# analogBoardV1_5.net
KiCad netlist of a schematic drawn in EAGLE
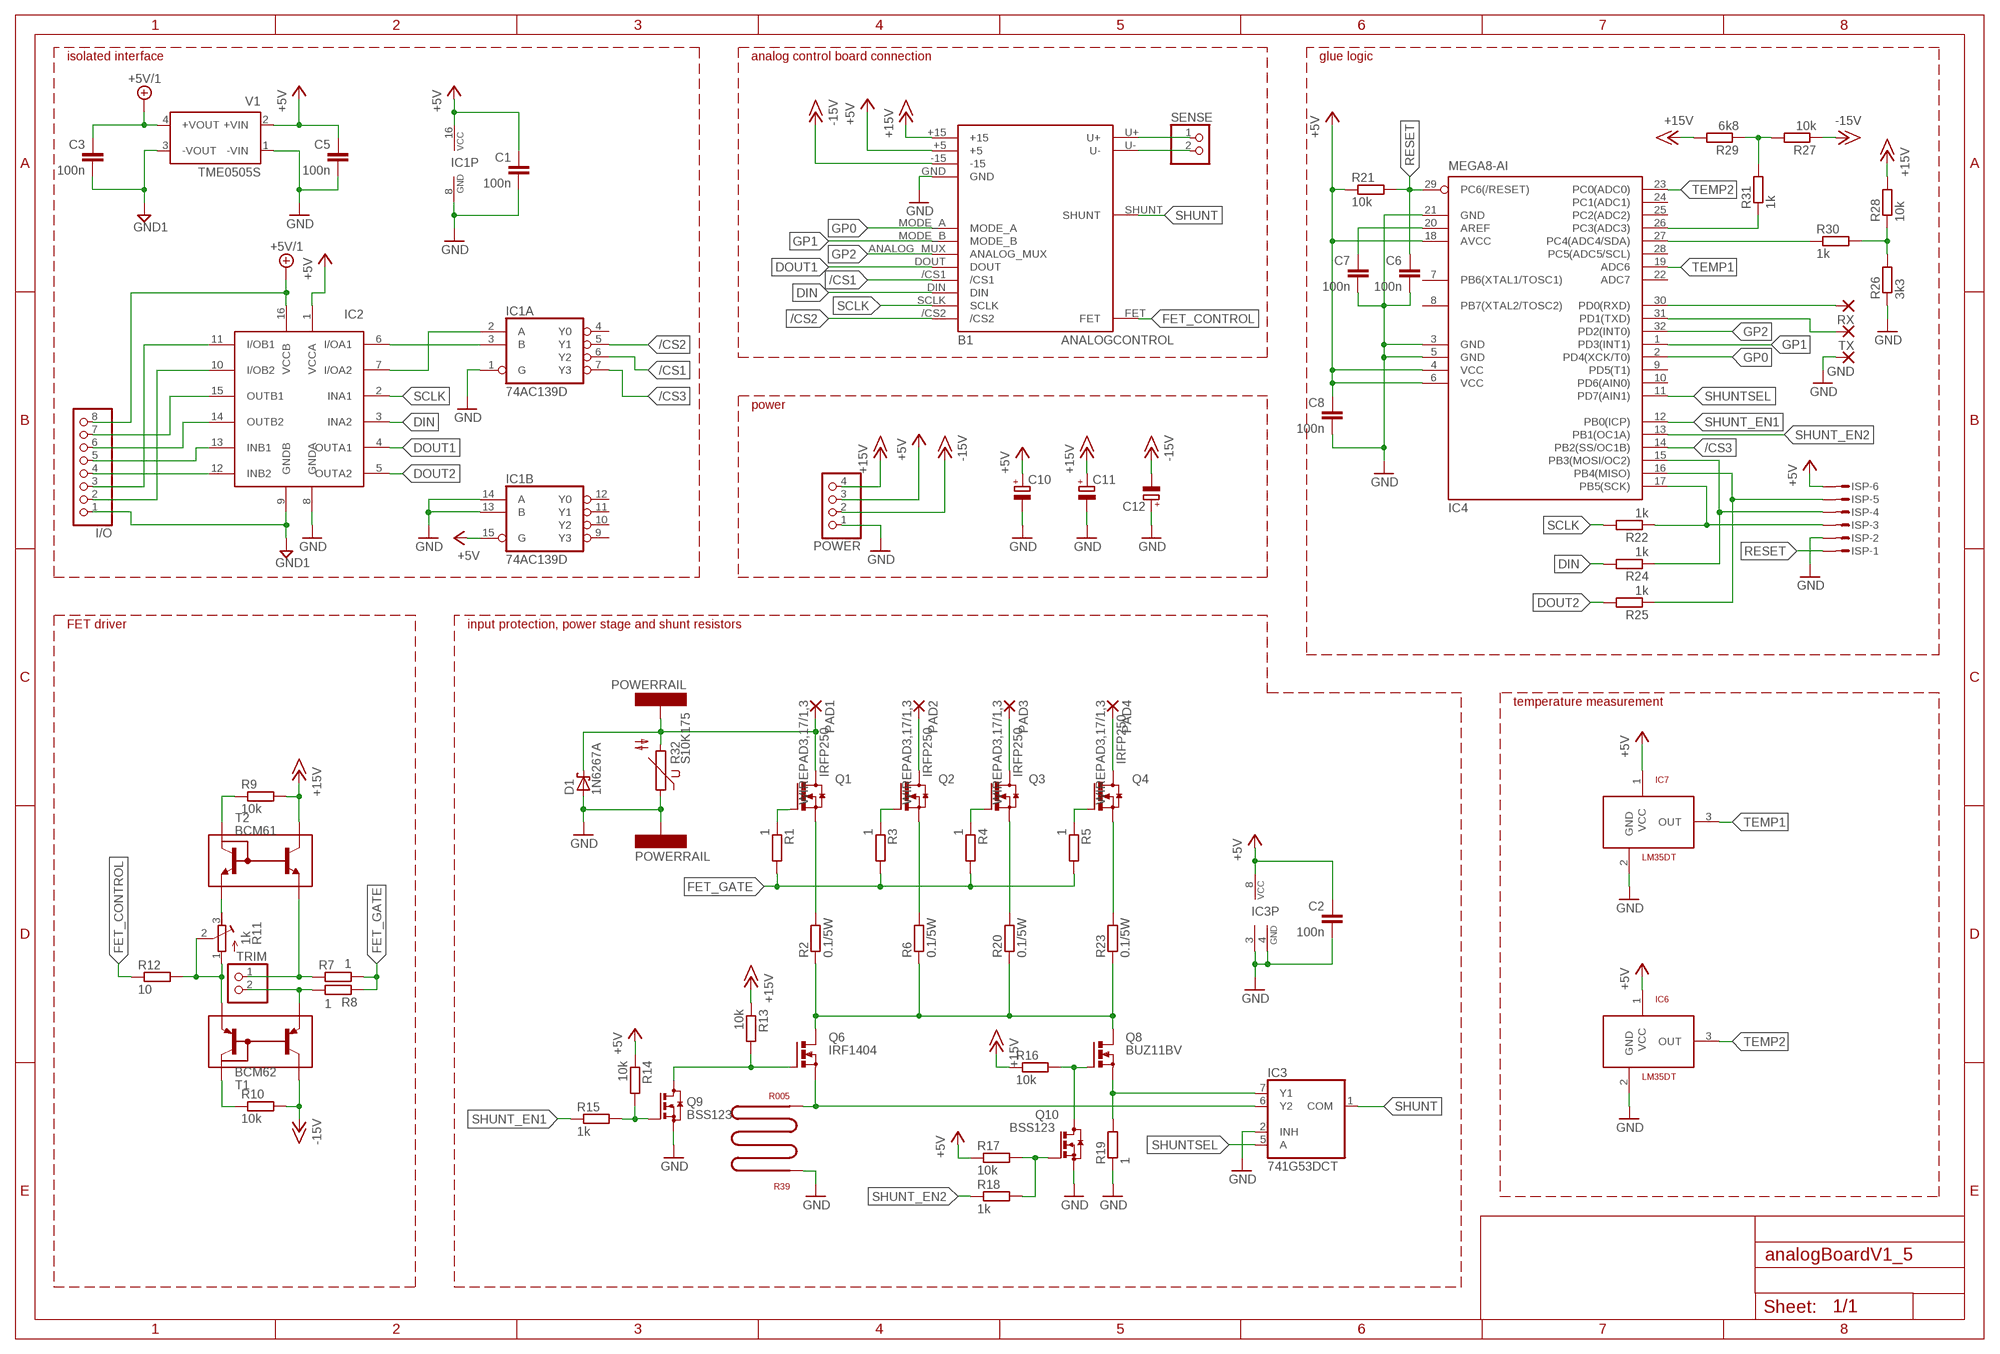
[diagram p0: schematic, sheet 1]

(export (version "E")
  (design (tool "Eeschema 10.0.6"))
  (components
    (comp (ref "B1")
      (value "ANALOGCONTROL")
      (footprint "eagle-import:ANALOGCONTROL")
      (libsource (lib "eagle-import") (part "ANALOGCONTROL"))
    )
    (comp (ref "C1")
      (value "100n")
      (footprint "eagle-import:C0603K")
      (libsource (lib "eagle-import") (part "C-EUC0603K"))
    )
    (comp (ref "C2")
      (value "100n")
      (footprint "eagle-import:C0603K")
      (libsource (lib "eagle-import") (part "C-EUC0603K"))
    )
    (comp (ref "C3")
      (value "100n")
      (footprint "eagle-import:C0603K")
      (libsource (lib "eagle-import") (part "C-EUC0603K"))
    )
    (comp (ref "C5")
      (value "100n")
      (footprint "eagle-import:C0603K")
      (libsource (lib "eagle-import") (part "C-EUC0603K"))
    )
    (comp (ref "C6")
      (value "100n")
      (footprint "eagle-import:C0603K")
      (libsource (lib "eagle-import") (part "C-EUC0603K"))
    )
    (comp (ref "C7")
      (value "100n")
      (footprint "eagle-import:C0603K")
      (libsource (lib "eagle-import") (part "C-EUC0603K"))
    )
    (comp (ref "C8")
      (value "100n")
      (footprint "eagle-import:C0603K")
      (libsource (lib "eagle-import") (part "C-EUC0603K"))
    )
    (comp (ref "C10")
      (value "CPOL-EUE2.5-6")
      (footprint "eagle-import:E2,5-6")
      (libsource (lib "eagle-import") (part "CPOL-EUE2.5-6"))
    )
    (comp (ref "C11")
      (value "CPOL-EUE2.5-6")
      (footprint "eagle-import:E2,5-6")
      (libsource (lib "eagle-import") (part "CPOL-EUE2.5-6"))
    )
    (comp (ref "C12")
      (value "CPOL-EUE2.5-6")
      (footprint "eagle-import:E2,5-6")
      (libsource (lib "eagle-import") (part "CPOL-EUE2.5-6"))
    )
    (comp (ref "D1")
      (value "1N6267A")
      (footprint "eagle-import:C4111-15")
      (libsource (lib "eagle-import") (part "1N6267A"))
    )
    (comp (ref "GND")
      (value "SMD2")
      (footprint "eagle-import:SMD1,27-2,54")
      (libsource (lib "eagle-import") (part "SMD2"))
    )
    (comp (ref "I/O")
      (value "PINHD-1X8")
      (footprint "eagle-import:1X08")
      (libsource (lib "eagle-import") (part "PINHD-1X8"))
    )
    (comp (ref "IC1")
      (value "74AC139D")
      (footprint "eagle-import:SO16")
      (libsource (lib "eagle-import") (part "74139DAC"))
    )
    (comp (ref "IC2")
      (value "MAX14850")
      (footprint "eagle-import:SOIC16N")
      (libsource (lib "eagle-import") (part "MAX14850"))
    )
    (comp (ref "IC3")
      (value "741G53DCT")
      (footprint "eagle-import:DCT_R-PDSO-G8")
      (libsource (lib "eagle-import") (part "741G53DCT"))
    )
    (comp (ref "IC4")
      (value "MEGA8-AI")
      (footprint "eagle-import:TQFP32-08")
      (fields (field (name "MPN") "ATMEGA8-16AU"))
      (libsource (lib "eagle-import") (part "MEGA8-AI"))
    )
    (comp (ref "IC6")
      (value "LM35DT")
      (footprint "eagle-import:TO220V")
      (libsource (lib "eagle-import") (part "LM35DT"))
    )
    (comp (ref "IC7")
      (value "LM35DT")
      (footprint "eagle-import:TO220V")
      (libsource (lib "eagle-import") (part "LM35DT"))
    )
    (comp (ref "ISP")
      (value "MICROMATCH-6SMF")
      (footprint "eagle-import:MMT-F-SMD-6")
      (libsource (lib "eagle-import") (part "MICROMATCH-6SMF"))
    )
    (comp (ref "PAD1")
      (value "WIREPAD3,17/1,3")
      (footprint "eagle-import:3,17_1,3")
      (libsource (lib "eagle-import") (part "WIREPAD3,17/1,3"))
    )
    (comp (ref "PAD2")
      (value "WIREPAD3,17/1,3")
      (footprint "eagle-import:3,17_1,3")
      (libsource (lib "eagle-import") (part "WIREPAD3,17/1,3"))
    )
    (comp (ref "PAD3")
      (value "WIREPAD3,17/1,3")
      (footprint "eagle-import:3,17_1,3")
      (libsource (lib "eagle-import") (part "WIREPAD3,17/1,3"))
    )
    (comp (ref "PAD4")
      (value "WIREPAD3,17/1,3")
      (footprint "eagle-import:3,17_1,3")
      (libsource (lib "eagle-import") (part "WIREPAD3,17/1,3"))
    )
    (comp (ref "POWER")
      (value "PINHD-1X4")
      (footprint "eagle-import:1X04")
      (libsource (lib "eagle-import") (part "PINHD-1X4"))
    )
    (comp (ref "Q1")
      (value "IRFP250")
      (footprint "eagle-import:TO-247AD-V")
      (libsource (lib "eagle-import") (part "IRFP250"))
    )
    (comp (ref "Q2")
      (value "IRFP250")
      (footprint "eagle-import:TO-247AD-V")
      (libsource (lib "eagle-import") (part "IRFP250"))
    )
    (comp (ref "Q3")
      (value "IRFP250")
      (footprint "eagle-import:TO-247AD-V")
      (libsource (lib "eagle-import") (part "IRFP250"))
    )
    (comp (ref "Q4")
      (value "IRFP250")
      (footprint "eagle-import:TO-247AD-V")
      (libsource (lib "eagle-import") (part "IRFP250"))
    )
    (comp (ref "Q6")
      (value "IRF1404")
      (footprint "eagle-import:TO220BV")
      (libsource (lib "eagle-import") (part "BUZ11BV"))
    )
    (comp (ref "Q8")
      (value "BUZ11BV")
      (footprint "eagle-import:TO220BV")
      (libsource (lib "eagle-import") (part "BUZ11BV"))
    )
    (comp (ref "Q9")
      (value "BSS123")
      (footprint "eagle-import:SOT23")
      (libsource (lib "eagle-import") (part "BSS123"))
    )
    (comp (ref "Q10")
      (value "BSS123")
      (footprint "eagle-import:SOT23")
      (libsource (lib "eagle-import") (part "BSS123"))
    )
    (comp (ref "R1")
      (value "1")
      (footprint "eagle-import:R0603")
      (libsource (lib "eagle-import") (part "resistor_R-EU_R0603"))
    )
    (comp (ref "R2")
      (value "0.1/5W")
      (footprint "eagle-import:5WAXIAL_H")
      (libsource (lib "eagle-import") (part "5WAXIALH"))
    )
    (comp (ref "R3")
      (value "1")
      (footprint "eagle-import:R0603")
      (libsource (lib "eagle-import") (part "resistor_R-EU_R0603"))
    )
    (comp (ref "R4")
      (value "1")
      (footprint "eagle-import:R0603")
      (libsource (lib "eagle-import") (part "resistor_R-EU_R0603"))
    )
    (comp (ref "R5")
      (value "1")
      (footprint "eagle-import:R0603")
      (libsource (lib "eagle-import") (part "resistor_R-EU_R0603"))
    )
    (comp (ref "R6")
      (value "0.1/5W")
      (footprint "eagle-import:5WAXIAL_H")
      (libsource (lib "eagle-import") (part "5WAXIALH"))
    )
    (comp (ref "R7")
      (value "1")
      (footprint "eagle-import:R0603")
      (libsource (lib "eagle-import") (part "resistor_R-EU_R0603"))
    )
    (comp (ref "R8")
      (value "1")
      (footprint "eagle-import:R0603")
      (libsource (lib "eagle-import") (part "resistor_R-EU_R0603"))
    )
    (comp (ref "R9")
      (value "10k")
      (footprint "eagle-import:R0603")
      (libsource (lib "eagle-import") (part "resistor_R-EU_R0603"))
    )
    (comp (ref "R10")
      (value "10k")
      (footprint "eagle-import:R0603")
      (libsource (lib "eagle-import") (part "resistor_R-EU_R0603"))
    )
    (comp (ref "R11")
      (value "1k")
      (footprint "eagle-import:RTRIM64W")
      (libsource (lib "eagle-import") (part "R-TRIMM64W"))
    )
    (comp (ref "R12")
      (value "10")
      (footprint "eagle-import:R0603")
      (libsource (lib "eagle-import") (part "resistor_R-EU_R0603"))
    )
    (comp (ref "R13")
      (value "10k")
      (footprint "eagle-import:R0603")
      (libsource (lib "eagle-import") (part "resistor_R-EU_R0603"))
    )
    (comp (ref "R14")
      (value "10k")
      (footprint "eagle-import:R0603")
      (libsource (lib "eagle-import") (part "resistor_R-EU_R0603"))
    )
    (comp (ref "R15")
      (value "1k")
      (footprint "eagle-import:R0603")
      (libsource (lib "eagle-import") (part "resistor_R-EU_R0603"))
    )
    (comp (ref "R16")
      (value "10k")
      (footprint "eagle-import:R0603")
      (libsource (lib "eagle-import") (part "resistor_R-EU_R0603"))
    )
    (comp (ref "R17")
      (value "10k")
      (footprint "eagle-import:R0603")
      (libsource (lib "eagle-import") (part "resistor_R-EU_R0603"))
    )
    (comp (ref "R18")
      (value "1k")
      (footprint "eagle-import:R0603")
      (libsource (lib "eagle-import") (part "resistor_R-EU_R0603"))
    )
    (comp (ref "R19")
      (value "1")
      (footprint "eagle-import:0414_15")
      (libsource (lib "eagle-import") (part "R-EU_0414/15"))
    )
    (comp (ref "R20")
      (value "0.1/5W")
      (footprint "eagle-import:5WAXIAL_H")
      (libsource (lib "eagle-import") (part "5WAXIALH"))
    )
    (comp (ref "R21")
      (value "10k")
      (footprint "eagle-import:R0603")
      (libsource (lib "eagle-import") (part "resistor_R-EU_R0603"))
    )
    (comp (ref "R22")
      (value "1k")
      (footprint "eagle-import:R0603")
      (libsource (lib "eagle-import") (part "resistor_R-EU_R0603"))
    )
    (comp (ref "R23")
      (value "0.1/5W")
      (footprint "eagle-import:5WAXIAL_H")
      (libsource (lib "eagle-import") (part "5WAXIALH"))
    )
    (comp (ref "R24")
      (value "1k")
      (footprint "eagle-import:R0603")
      (libsource (lib "eagle-import") (part "resistor_R-EU_R0603"))
    )
    (comp (ref "R25")
      (value "1k")
      (footprint "eagle-import:R0603")
      (libsource (lib "eagle-import") (part "resistor_R-EU_R0603"))
    )
    (comp (ref "R26")
      (value "3k3")
      (footprint "eagle-import:R0603")
      (libsource (lib "eagle-import") (part "resistor_R-EU_R0603"))
    )
    (comp (ref "R27")
      (value "10k")
      (footprint "eagle-import:R0603")
      (libsource (lib "eagle-import") (part "resistor_R-EU_R0603"))
    )
    (comp (ref "R28")
      (value "10k")
      (footprint "eagle-import:R0603")
      (libsource (lib "eagle-import") (part "resistor_R-EU_R0603"))
    )
    (comp (ref "R29")
      (value "6k8")
      (footprint "eagle-import:R0603")
      (libsource (lib "eagle-import") (part "resistor_R-EU_R0603"))
    )
    (comp (ref "R30")
      (value "1k")
      (footprint "eagle-import:R0603")
      (libsource (lib "eagle-import") (part "resistor_R-EU_R0603"))
    )
    (comp (ref "R31")
      (value "1k")
      (footprint "eagle-import:R0603")
      (libsource (lib "eagle-import") (part "resistor_R-EU_R0603"))
    )
    (comp (ref "R32")
      (value "S10K175")
      (footprint "eagle-import:S10K175")
      (libsource (lib "eagle-import") (part "S10K175"))
    )
    (comp (ref "R39")
      (value "R005")
      (footprint "eagle-import:PWR4412-2S")
      (libsource (lib "eagle-import") (part "SHUNTPWR"))
    )
    (comp (ref "RX")
      (value "SMD2")
      (footprint "eagle-import:SMD1,27-2,54")
      (libsource (lib "eagle-import") (part "SMD2"))
    )
    (comp (ref "SENSE")
      (value "PINHD-1X2")
      (footprint "eagle-import:1X02")
      (libsource (lib "eagle-import") (part "PINHD-1X2"))
    )
    (comp (ref "T1")
      (value "BCM62")
      (footprint "eagle-import:SOT143B")
      (libsource (lib "eagle-import") (part "BCM62"))
    )
    (comp (ref "T2")
      (value "BCM61")
      (footprint "eagle-import:SOT143B")
      (libsource (lib "eagle-import") (part "BCM61"))
    )
    (comp (ref "TRIM")
      (value "PINHD-1X2")
      (footprint "eagle-import:1X02")
      (libsource (lib "eagle-import") (part "PINHD-1X2"))
    )
    (comp (ref "TX")
      (value "SMD2")
      (footprint "eagle-import:SMD1,27-2,54")
      (libsource (lib "eagle-import") (part "SMD2"))
    )
    (comp (ref "U$1")
      (value "POWERRAIL")
      (footprint "eagle-import:POWERRAIL")
      (libsource (lib "eagle-import") (part "POWERRAIL"))
    )
    (comp (ref "U$2")
      (value "POWERRAIL")
      (footprint "eagle-import:POWERRAIL")
      (libsource (lib "eagle-import") (part "POWERRAIL"))
    )
    (comp (ref "V1")
      (value "TME0505S")
      (footprint "eagle-import:TME")
      (fields (field (name "MPN") "TME 0505S"))
      (libsource (lib "eagle-import") (part "TME?0505S"))
    )
  )
  (nets
    (net (code "1") (name "+5V") (class "Default")
      (node (ref "B1") (pin "+5") (pinfunction "+5_+5") (pintype "bidirectional"))
      (node (ref "C1") (pin "1") (pinfunction "1_1") (pintype "passive"))
      (node (ref "C10") (pin "+") (pinfunction "+_+") (pintype "passive"))
      (node (ref "C2") (pin "1") (pinfunction "1_1") (pintype "passive"))
      (node (ref "C5") (pin "1") (pinfunction "1_1") (pintype "passive"))
      (node (ref "C8") (pin "1") (pinfunction "1_1") (pintype "passive"))
      (node (ref "IC1") (pin "15") (pinfunction "G_15") (pintype "input"))
      (node (ref "IC1") (pin "16") (pinfunction "VCC_16") (pintype "power_in"))
      (node (ref "IC2") (pin "1") (pinfunction "VCCA_1") (pintype "bidirectional"))
      (node (ref "IC3") (pin "8") (pinfunction "VCC_8") (pintype "power_in"))
      (node (ref "IC4") (pin "18") (pinfunction "AVCC_18") (pintype "power_in"))
      (node (ref "IC4") (pin "4") (pinfunction "VCC_4") (pintype "power_in"))
      (node (ref "IC4") (pin "6") (pinfunction "VCC_6") (pintype "power_in"))
      (node (ref "IC6") (pin "1") (pinfunction "VCC_1") (pintype "bidirectional"))
      (node (ref "IC7") (pin "1") (pinfunction "VCC_1") (pintype "bidirectional"))
      (node (ref "ISP") (pin "6") (pinfunction "S_6") (pintype "passive"))
      (node (ref "POWER") (pin "3") (pinfunction "3_3") (pintype "passive"))
      (node (ref "R14") (pin "1") (pinfunction "1_1") (pintype "passive"))
      (node (ref "R17") (pin "1") (pinfunction "1_1") (pintype "passive"))
      (node (ref "R21") (pin "1") (pinfunction "1_1") (pintype "passive"))
      (node (ref "V1") (pin "2") (pinfunction "+VIN_2") (pintype "passive"))
    )
    (net (code "2") (name "+5V{slash}1") (class "Default")
      (node (ref "C3") (pin "1") (pinfunction "1_1") (pintype "passive"))
      (node (ref "I/O") (pin "8") (pinfunction "8_8") (pintype "passive"))
      (node (ref "IC2") (pin "16") (pinfunction "VCCB_16") (pintype "bidirectional"))
      (node (ref "V1") (pin "4") (pinfunction "+VOUT_4") (pintype "passive"))
    )
    (net (code "3") (name "+15V") (class "Default")
      (node (ref "B1") (pin "+15") (pinfunction "+15_+15") (pintype "bidirectional"))
      (node (ref "C11") (pin "+") (pinfunction "+_+") (pintype "passive"))
      (node (ref "POWER") (pin "4") (pinfunction "4_4") (pintype "passive"))
      (node (ref "R13") (pin "1") (pinfunction "1_1") (pintype "passive"))
      (node (ref "R16") (pin "1") (pinfunction "1_1") (pintype "passive"))
      (node (ref "R28") (pin "2") (pinfunction "2_2") (pintype "passive"))
      (node (ref "R29") (pin "2") (pinfunction "2_2") (pintype "passive"))
      (node (ref "R9") (pin "2") (pinfunction "2_2") (pintype "passive"))
      (node (ref "T2") (pin "2") (pinfunction "2_2") (pintype "bidirectional"))
    )
    (net (code "4") (name "-15V") (class "Default")
      (node (ref "B1") (pin "-15") (pinfunction "-15_-15") (pintype "bidirectional"))
      (node (ref "C12") (pin "-") (pinfunction "-_-") (pintype "passive"))
      (node (ref "POWER") (pin "2") (pinfunction "2_2") (pintype "passive"))
      (node (ref "R10") (pin "2") (pinfunction "2_2") (pintype "passive"))
      (node (ref "R27") (pin "1") (pinfunction "1_1") (pintype "passive"))
      (node (ref "T1") (pin "2") (pinfunction "2_2") (pintype "bidirectional"))
    )
    (net (code "5") (name "DIN") (class "Default")
      (node (ref "B1") (pin "DIN") (pinfunction "DIN_DIN") (pintype "bidirectional"))
      (node (ref "IC2") (pin "3") (pinfunction "INA2_3") (pintype "bidirectional"))
      (node (ref "R24") (pin "2") (pinfunction "2_2") (pintype "passive"))
    )
    (net (code "6") (name "DOUT1") (class "Default")
      (node (ref "B1") (pin "DOUT") (pinfunction "DOUT_DOUT") (pintype "bidirectional"))
      (node (ref "IC2") (pin "4") (pinfunction "OUTA1_4") (pintype "bidirectional"))
    )
    (net (code "7") (name "DOUT2") (class "Default")
      (node (ref "IC2") (pin "5") (pinfunction "OUTA2_5") (pintype "bidirectional"))
      (node (ref "R25") (pin "2") (pinfunction "2_2") (pintype "passive"))
    )
    (net (code "8") (name "FET_CONTROL") (class "Default")
      (node (ref "B1") (pin "FET") (pinfunction "FET_FET") (pintype "bidirectional"))
      (node (ref "R12") (pin "1") (pinfunction "1_1") (pintype "passive"))
    )
    (net (code "9") (name "FET_GATE") (class "Default")
      (node (ref "R1") (pin "2") (pinfunction "2_2") (pintype "passive"))
      (node (ref "R3") (pin "2") (pinfunction "2_2") (pintype "passive"))
      (node (ref "R4") (pin "2") (pinfunction "2_2") (pintype "passive"))
      (node (ref "R5") (pin "2") (pinfunction "2_2") (pintype "passive"))
      (node (ref "R7") (pin "2") (pinfunction "2_2") (pintype "passive"))
      (node (ref "R8") (pin "1") (pinfunction "1_1") (pintype "passive"))
    )
    (net (code "10") (name "GND") (class "Default")
      (node (ref "B1") (pin "GND") (pinfunction "GND_GND") (pintype "bidirectional"))
      (node (ref "C1") (pin "2") (pinfunction "2_2") (pintype "passive"))
      (node (ref "C10") (pin "-") (pinfunction "-_-") (pintype "passive"))
      (node (ref "C11") (pin "-") (pinfunction "-_-") (pintype "passive"))
      (node (ref "C12") (pin "+") (pinfunction "+_+") (pintype "passive"))
      (node (ref "C2") (pin "2") (pinfunction "2_2") (pintype "passive"))
      (node (ref "C5") (pin "2") (pinfunction "2_2") (pintype "passive"))
      (node (ref "C6") (pin "2") (pinfunction "2_2") (pintype "passive"))
      (node (ref "C7") (pin "2") (pinfunction "2_2") (pintype "passive"))
      (node (ref "C8") (pin "2") (pinfunction "2_2") (pintype "passive"))
      (node (ref "D1") (pin "A") (pinfunction "A_A") (pintype "passive"))
      (node (ref "GND") (pin "1") (pinfunction "P_1") (pintype "passive"))
      (node (ref "IC1") (pin "1") (pinfunction "G_1") (pintype "input"))
      (node (ref "IC1") (pin "13") (pinfunction "B_13") (pintype "input"))
      (node (ref "IC1") (pin "14") (pinfunction "A_14") (pintype "input"))
      (node (ref "IC1") (pin "8") (pinfunction "GND_8") (pintype "power_in"))
      (node (ref "IC2") (pin "8") (pinfunction "GNDA_8") (pintype "bidirectional"))
      (node (ref "IC3") (pin "2") (pinfunction "INH_2") (pintype "input"))
      (node (ref "IC3") (pin "3") (pinfunction "GND_3") (pintype "power_in"))
      (node (ref "IC3") (pin "4") (pinfunction "GND_4") (pintype "power_in"))
      (node (ref "IC4") (pin "21") (pinfunction "GND_21") (pintype "power_in"))
      (node (ref "IC4") (pin "3") (pinfunction "GND_3") (pintype "power_in"))
      (node (ref "IC4") (pin "5") (pinfunction "GND_5") (pintype "power_in"))
      (node (ref "IC6") (pin "2") (pinfunction "GND_2") (pintype "bidirectional"))
      (node (ref "IC7") (pin "2") (pinfunction "GND_2") (pintype "bidirectional"))
      (node (ref "ISP") (pin "2") (pinfunction "S_2") (pintype "passive"))
      (node (ref "POWER") (pin "1") (pinfunction "1_1") (pintype "passive"))
      (node (ref "Q10") (pin "2") (pinfunction "S_2") (pintype "passive"))
      (node (ref "Q9") (pin "2") (pinfunction "S_2") (pintype "passive"))
      (node (ref "R19") (pin "1") (pinfunction "1_1") (pintype "passive"))
      (node (ref "R26") (pin "1") (pinfunction "1_1") (pintype "passive"))
      (node (ref "R32") (pin "1") (pinfunction "1_1") (pintype "passive"))
      (node (ref "R39") (pin "P$1") (pinfunction "P$1_P$1") (pintype "bidirectional"))
      (node (ref "U$2") (pin "1") (pinfunction "P$1_1") (pintype "bidirectional"))
      (node (ref "V1") (pin "1") (pinfunction "-VIN_1") (pintype "passive"))
    )
    (net (code "11") (name "GND1") (class "Default")
      (node (ref "C3") (pin "2") (pinfunction "2_2") (pintype "passive"))
      (node (ref "I/O") (pin "1") (pinfunction "1_1") (pintype "passive"))
      (node (ref "IC2") (pin "9") (pinfunction "GNDB_9") (pintype "bidirectional"))
      (node (ref "V1") (pin "3") (pinfunction "-VOUT_3") (pintype "passive"))
    )
    (net (code "12") (name "GP0") (class "Default")
      (node (ref "B1") (pin "MODE_A") (pinfunction "MODE_A_MODE_A") (pintype "bidirectional"))
      (node (ref "IC4") (pin "2") (pinfunction "PD4(XCK/T0)_2") (pintype "bidirectional"))
    )
    (net (code "13") (name "GP1") (class "Default")
      (node (ref "B1") (pin "MODE_B") (pinfunction "MODE_B_MODE_B") (pintype "bidirectional"))
      (node (ref "IC4") (pin "1") (pinfunction "PD3(INT1)_1") (pintype "bidirectional"))
    )
    (net (code "14") (name "GP2") (class "Default")
      (node (ref "B1") (pin "ANALOG_MUX") (pinfunction "ANALOG_MUX_ANALOG_MUX") (pintype "bidirectional"))
      (node (ref "IC4") (pin "32") (pinfunction "PD2(INT0)_32") (pintype "bidirectional"))
    )
    (net (code "15") (name "Net-(B1-PadU+)") (class "Default")
      (node (ref "B1") (pin "U+") (pinfunction "U+_U+") (pintype "bidirectional"))
      (node (ref "SENSE") (pin "1") (pinfunction "1_1") (pintype "passive"))
    )
    (net (code "16") (name "Net-(B1-PadU-)") (class "Default")
      (node (ref "B1") (pin "U-") (pinfunction "U-_U-") (pintype "bidirectional"))
      (node (ref "SENSE") (pin "2") (pinfunction "2_2") (pintype "passive"))
    )
    (net (code "17") (name "Net-(IC1A-A)") (class "Default")
      (node (ref "IC1") (pin "2") (pinfunction "A_2") (pintype "input"))
      (node (ref "IC2") (pin "7") (pinfunction "I/OA2_7") (pintype "bidirectional"))
    )
    (net (code "18") (name "Net-(IC1A-B)") (class "Default")
      (node (ref "IC1") (pin "3") (pinfunction "B_3") (pintype "input"))
      (node (ref "IC2") (pin "6") (pinfunction "I/OA1_6") (pintype "bidirectional"))
    )
    (net (code "19") (name "Net-(IC2-INB1)") (class "Default")
      (node (ref "I/O") (pin "5") (pinfunction "5_5") (pintype "passive"))
      (node (ref "IC2") (pin "13") (pinfunction "INB1_13") (pintype "bidirectional"))
    )
    (net (code "20") (name "Net-(IC2-INB2)") (class "Default")
      (node (ref "I/O") (pin "4") (pinfunction "4_4") (pintype "passive"))
      (node (ref "IC2") (pin "12") (pinfunction "INB2_12") (pintype "bidirectional"))
    )
    (net (code "21") (name "Net-(IC2-I{slash}OB1)") (class "Default")
      (node (ref "I/O") (pin "3") (pinfunction "3_3") (pintype "passive"))
      (node (ref "IC2") (pin "11") (pinfunction "I/OB1_11") (pintype "bidirectional"))
    )
    (net (code "22") (name "Net-(IC2-I{slash}OB2)") (class "Default")
      (node (ref "I/O") (pin "2") (pinfunction "2_2") (pintype "passive"))
      (node (ref "IC2") (pin "10") (pinfunction "I/OB2_10") (pintype "bidirectional"))
    )
    (net (code "23") (name "Net-(IC2-OUTB1)") (class "Default")
      (node (ref "I/O") (pin "7") (pinfunction "7_7") (pintype "passive"))
      (node (ref "IC2") (pin "15") (pinfunction "OUTB1_15") (pintype "bidirectional"))
    )
    (net (code "24") (name "Net-(IC2-OUTB2)") (class "Default")
      (node (ref "I/O") (pin "6") (pinfunction "6_6") (pintype "passive"))
      (node (ref "IC2") (pin "14") (pinfunction "OUTB2_14") (pintype "bidirectional"))
    )
    (net (code "25") (name "Net-(IC3A-Y1)") (class "Default")
      (node (ref "IC3") (pin "7") (pinfunction "Y1_7") (pintype "bidirectional"))
      (node (ref "Q8") (pin "S") (pinfunction "S_S") (pintype "passive"))
      (node (ref "R19") (pin "2") (pinfunction "2_2") (pintype "passive"))
    )
    (net (code "26") (name "Net-(IC3A-Y2)") (class "Default")
      (node (ref "IC3") (pin "6") (pinfunction "Y2_6") (pintype "bidirectional"))
      (node (ref "Q6") (pin "S") (pinfunction "S_S") (pintype "passive"))
      (node (ref "R39") (pin "P$2") (pinfunction "P$2_P$2") (pintype "bidirectional"))
    )
    (net (code "27") (name "Net-(IC4-AREF)") (class "Default")
      (node (ref "C7") (pin "1") (pinfunction "1_1") (pintype "passive"))
      (node (ref "IC4") (pin "20") (pinfunction "AREF_20") (pintype "passive"))
    )
    (net (code "28") (name "Net-(IC4-PB3(MOSI{slash}OC2))") (class "Default")
      (node (ref "IC4") (pin "15") (pinfunction "PB3(MOSI/OC2)_15") (pintype "bidirectional"))
      (node (ref "ISP") (pin "4") (pinfunction "S_4") (pintype "passive"))
      (node (ref "R24") (pin "1") (pinfunction "1_1") (pintype "passive"))
    )
    (net (code "29") (name "Net-(IC4-PB4(MISO))") (class "Default")
      (node (ref "IC4") (pin "16") (pinfunction "PB4(MISO)_16") (pintype "bidirectional"))
      (node (ref "ISP") (pin "5") (pinfunction "S_5") (pintype "passive"))
      (node (ref "R25") (pin "1") (pinfunction "1_1") (pintype "passive"))
    )
    (net (code "30") (name "Net-(IC4-PB5(SCK))") (class "Default")
      (node (ref "IC4") (pin "17") (pinfunction "PB5(SCK)_17") (pintype "bidirectional"))
      (node (ref "ISP") (pin "3") (pinfunction "S_3") (pintype "passive"))
      (node (ref "R22") (pin "1") (pinfunction "1_1") (pintype "passive"))
    )
    (net (code "31") (name "Net-(IC4-PC3(ADC3))") (class "Default")
      (node (ref "IC4") (pin "26") (pinfunction "PC3(ADC3)_26") (pintype "bidirectional"))
      (node (ref "R31") (pin "1") (pinfunction "1_1") (pintype "passive"))
    )
    (net (code "32") (name "Net-(IC4-PC4(ADC4{slash}SDA))") (class "Default")
      (node (ref "IC4") (pin "27") (pinfunction "PC4(ADC4/SDA)_27") (pintype "bidirectional"))
      (node (ref "R30") (pin "1") (pinfunction "1_1") (pintype "passive"))
    )
    (net (code "33") (name "Net-(IC4-PD0(RXD))") (class "Default")
      (node (ref "IC4") (pin "30") (pinfunction "PD0(RXD)_30") (pintype "bidirectional"))
      (node (ref "RX") (pin "1") (pinfunction "P_1") (pintype "passive"))
    )
    (net (code "34") (name "Net-(IC4-PD1(TXD))") (class "Default")
      (node (ref "IC4") (pin "31") (pinfunction "PD1(TXD)_31") (pintype "bidirectional"))
      (node (ref "TX") (pin "1") (pinfunction "P_1") (pintype "passive"))
    )
    (net (code "35") (name "Net-(PAD1-P)") (class "Default")
      (node (ref "D1") (pin "C") (pinfunction "C_C") (pintype "passive"))
      (node (ref "PAD1") (pin "1") (pinfunction "P_1") (pintype "passive"))
      (node (ref "Q1") (pin "D") (pinfunction "D_D") (pintype "passive"))
      (node (ref "R32") (pin "2") (pinfunction "2_2") (pintype "passive"))
      (node (ref "U$1") (pin "1") (pinfunction "P$1_1") (pintype "bidirectional"))
    )
    (net (code "36") (name "Net-(PAD2-P)") (class "Default")
      (node (ref "PAD2") (pin "1") (pinfunction "P_1") (pintype "passive"))
      (node (ref "Q2") (pin "D") (pinfunction "D_D") (pintype "passive"))
    )
    (net (code "37") (name "Net-(PAD3-P)") (class "Default")
      (node (ref "PAD3") (pin "1") (pinfunction "P_1") (pintype "passive"))
      (node (ref "Q3") (pin "D") (pinfunction "D_D") (pintype "passive"))
    )
    (net (code "38") (name "Net-(PAD4-P)") (class "Default")
      (node (ref "PAD4") (pin "1") (pinfunction "P_1") (pintype "passive"))
      (node (ref "Q4") (pin "D") (pinfunction "D_D") (pintype "passive"))
    )
    (net (code "39") (name "Net-(Q1-PadG)") (class "Default")
      (node (ref "Q1") (pin "G") (pinfunction "G_G") (pintype "passive"))
      (node (ref "R1") (pin "1") (pinfunction "1_1") (pintype "passive"))
    )
    (net (code "40") (name "Net-(Q1-PadS)") (class "Default")
      (node (ref "Q1") (pin "S") (pinfunction "S_S") (pintype "passive"))
      (node (ref "R2") (pin "2") (pinfunction "2_2") (pintype "passive"))
    )
    (net (code "41") (name "Net-(Q2-PadG)") (class "Default")
      (node (ref "Q2") (pin "G") (pinfunction "G_G") (pintype "passive"))
      (node (ref "R3") (pin "1") (pinfunction "1_1") (pintype "passive"))
    )
    (net (code "42") (name "Net-(Q2-PadS)") (class "Default")
      (node (ref "Q2") (pin "S") (pinfunction "S_S") (pintype "passive"))
      (node (ref "R6") (pin "2") (pinfunction "2_2") (pintype "passive"))
    )
    (net (code "43") (name "Net-(Q3-PadG)") (class "Default")
      (node (ref "Q3") (pin "G") (pinfunction "G_G") (pintype "passive"))
      (node (ref "R4") (pin "1") (pinfunction "1_1") (pintype "passive"))
    )
    (net (code "44") (name "Net-(Q3-PadS)") (class "Default")
      (node (ref "Q3") (pin "S") (pinfunction "S_S") (pintype "passive"))
      (node (ref "R20") (pin "2") (pinfunction "2_2") (pintype "passive"))
    )
    (net (code "45") (name "Net-(Q4-PadG)") (class "Default")
      (node (ref "Q4") (pin "G") (pinfunction "G_G") (pintype "passive"))
      (node (ref "R5") (pin "1") (pinfunction "1_1") (pintype "passive"))
    )
    (net (code "46") (name "Net-(Q4-PadS)") (class "Default")
      (node (ref "Q4") (pin "S") (pinfunction "S_S") (pintype "passive"))
      (node (ref "R23") (pin "2") (pinfunction "2_2") (pintype "passive"))
    )
    (net (code "47") (name "Net-(Q6-PadD)") (class "Default")
      (node (ref "Q6") (pin "D") (pinfunction "D_D") (pintype "passive"))
      (node (ref "Q8") (pin "D") (pinfunction "D_D") (pintype "passive"))
      (node (ref "R2") (pin "1") (pinfunction "1_1") (pintype "passive"))
      (node (ref "R20") (pin "1") (pinfunction "1_1") (pintype "passive"))
      (node (ref "R23") (pin "1") (pinfunction "1_1") (pintype "passive"))
      (node (ref "R6") (pin "1") (pinfunction "1_1") (pintype "passive"))
    )
    (net (code "48") (name "Net-(Q9-D)") (class "Default")
      (node (ref "Q6") (pin "G") (pinfunction "G_G") (pintype "passive"))
      (node (ref "Q9") (pin "3") (pinfunction "D_3") (pintype "passive"))
      (node (ref "R13") (pin "2") (pinfunction "2_2") (pintype "passive"))
    )
    (net (code "49") (name "Net-(Q9-G)") (class "Default")
      (node (ref "Q9") (pin "1") (pinfunction "G_1") (pintype "passive"))
      (node (ref "R14") (pin "2") (pinfunction "2_2") (pintype "passive"))
      (node (ref "R15") (pin "2") (pinfunction "2_2") (pintype "passive"))
    )
    (net (code "50") (name "Net-(Q10-D)") (class "Default")
      (node (ref "Q10") (pin "3") (pinfunction "D_3") (pintype "passive"))
      (node (ref "Q8") (pin "G") (pinfunction "G_G") (pintype "passive"))
      (node (ref "R16") (pin "2") (pinfunction "2_2") (pintype "passive"))
    )
    (net (code "51") (name "Net-(Q10-G)") (class "Default")
      (node (ref "Q10") (pin "1") (pinfunction "G_1") (pintype "passive"))
      (node (ref "R17") (pin "2") (pinfunction "2_2") (pintype "passive"))
      (node (ref "R18") (pin "2") (pinfunction "2_2") (pintype "passive"))
    )
    (net (code "52") (name "Net-(R7-Pad1)") (class "Default")
      (node (ref "R7") (pin "1") (pinfunction "1_1") (pintype "passive"))
      (node (ref "T2") (pin "3") (pinfunction "3_3") (pintype "bidirectional"))
      (node (ref "TRIM") (pin "1") (pinfunction "1_1") (pintype "passive"))
    )
    (net (code "53") (name "Net-(R8-Pad2)") (class "Default")
      (node (ref "R8") (pin "2") (pinfunction "2_2") (pintype "passive"))
      (node (ref "T1") (pin "3") (pinfunction "3_3") (pintype "bidirectional"))
      (node (ref "TRIM") (pin "2") (pinfunction "2_2") (pintype "passive"))
    )
    (net (code "54") (name "Net-(R9-Pad1)") (class "Default")
      (node (ref "R9") (pin "1") (pinfunction "1_1") (pintype "passive"))
      (node (ref "T2") (pin "1") (pinfunction "1_1") (pintype "bidirectional"))
    )
    (net (code "55") (name "Net-(R10-Pad1)") (class "Default")
      (node (ref "R10") (pin "1") (pinfunction "1_1") (pintype "passive"))
      (node (ref "T1") (pin "1") (pinfunction "1_1") (pintype "bidirectional"))
    )
    (net (code "56") (name "Net-(R11-A)") (class "Default")
      (node (ref "R11") (pin "3") (pinfunction "A_3") (pintype "passive"))
      (node (ref "T2") (pin "4") (pinfunction "4_4") (pintype "bidirectional"))
    )
    (net (code "57") (name "Net-(R11-E)") (class "Default")
      (node (ref "R11") (pin "1") (pinfunction "E_1") (pintype "passive"))
      (node (ref "R11") (pin "2") (pinfunction "S_2") (pintype "passive"))
      (node (ref "R12") (pin "2") (pinfunction "2_2") (pintype "passive"))
      (node (ref "T1") (pin "4") (pinfunction "4_4") (pintype "bidirectional"))
    )
    (net (code "58") (name "Net-(R26-Pad2)") (class "Default")
      (node (ref "R26") (pin "2") (pinfunction "2_2") (pintype "passive"))
      (node (ref "R28") (pin "1") (pinfunction "1_1") (pintype "passive"))
      (node (ref "R30") (pin "2") (pinfunction "2_2") (pintype "passive"))
    )
    (net (code "59") (name "Net-(R27-Pad2)") (class "Default")
      (node (ref "R27") (pin "2") (pinfunction "2_2") (pintype "passive"))
      (node (ref "R29") (pin "1") (pinfunction "1_1") (pintype "passive"))
      (node (ref "R31") (pin "2") (pinfunction "2_2") (pintype "passive"))
    )
    (net (code "60") (name "RESET") (class "Default")
      (node (ref "C6") (pin "1") (pinfunction "1_1") (pintype "passive"))
      (node (ref "IC4") (pin "29") (pinfunction "PC6(/RESET)_29") (pintype "bidirectional"))
      (node (ref "ISP") (pin "1") (pinfunction "S_1") (pintype "passive"))
      (node (ref "R21") (pin "2") (pinfunction "2_2") (pintype "passive"))
    )
    (net (code "61") (name "SCLK") (class "Default")
      (node (ref "B1") (pin "SCLK") (pinfunction "SCLK_SCLK") (pintype "bidirectional"))
      (node (ref "IC2") (pin "2") (pinfunction "INA1_2") (pintype "bidirectional"))
      (node (ref "R22") (pin "2") (pinfunction "2_2") (pintype "passive"))
    )
    (net (code "62") (name "SHUNT") (class "Default")
      (node (ref "B1") (pin "SHUNT") (pinfunction "SHUNT_SHUNT") (pintype "bidirectional"))
      (node (ref "IC3") (pin "1") (pinfunction "COM_1") (pintype "bidirectional"))
    )
    (net (code "63") (name "SHUNTSEL") (class "Default")
      (node (ref "IC3") (pin "5") (pinfunction "A_5") (pintype "input"))
      (node (ref "IC4") (pin "11") (pinfunction "PD7(AIN1)_11") (pintype "bidirectional"))
    )
    (net (code "64") (name "SHUNT_EN1") (class "Default")
      (node (ref "IC4") (pin "12") (pinfunction "PB0(ICP)_12") (pintype "bidirectional"))
      (node (ref "R15") (pin "1") (pinfunction "1_1") (pintype "passive"))
    )
    (net (code "65") (name "SHUNT_EN2") (class "Default")
      (node (ref "IC4") (pin "13") (pinfunction "PB1(OC1A)_13") (pintype "bidirectional"))
      (node (ref "R18") (pin "1") (pinfunction "1_1") (pintype "passive"))
    )
    (net (code "66") (name "TEMP1") (class "Default")
      (node (ref "IC4") (pin "19") (pinfunction "ADC6_19") (pintype "bidirectional"))
      (node (ref "IC7") (pin "3") (pinfunction "OUT_3") (pintype "bidirectional"))
    )
    (net (code "67") (name "TEMP2") (class "Default")
      (node (ref "IC4") (pin "23") (pinfunction "PC0(ADC0)_23") (pintype "bidirectional"))
      (node (ref "IC6") (pin "3") (pinfunction "OUT_3") (pintype "bidirectional"))
    )
    (net (code "68") (name "unconnected-(IC1A-Y0-Pad4)") (class "Default")
      (node (ref "IC1") (pin "4") (pinfunction "Y0_4") (pintype "output"))
    )
    (net (code "69") (name "unconnected-(IC1B-Y0-Pad12)") (class "Default")
      (node (ref "IC1") (pin "12") (pinfunction "Y0_12") (pintype "output"))
    )
    (net (code "70") (name "unconnected-(IC1B-Y1-Pad11)") (class "Default")
      (node (ref "IC1") (pin "11") (pinfunction "Y1_11") (pintype "output"))
    )
    (net (code "71") (name "unconnected-(IC1B-Y2-Pad10)") (class "Default")
      (node (ref "IC1") (pin "10") (pinfunction "Y2_10") (pintype "output"))
    )
    (net (code "72") (name "unconnected-(IC1B-Y3-Pad9)") (class "Default")
      (node (ref "IC1") (pin "9") (pinfunction "Y3_9") (pintype "output"))
    )
    (net (code "73") (name "unconnected-(IC4-ADC7-Pad22)") (class "Default")
      (node (ref "IC4") (pin "22") (pinfunction "ADC7_22") (pintype "bidirectional"))
    )
    (net (code "74") (name "unconnected-(IC4-PB6(XTAL1{slash}TOSC1)-Pad7)") (class "Default")
      (node (ref "IC4") (pin "7") (pinfunction "PB6(XTAL1/TOSC1)_7") (pintype "bidirectional"))
    )
    (net (code "75") (name "unconnected-(IC4-PB7(XTAL2{slash}TOSC2)-Pad8)") (class "Default")
      (node (ref "IC4") (pin "8") (pinfunction "PB7(XTAL2/TOSC2)_8") (pintype "bidirectional"))
    )
    (net (code "76") (name "unconnected-(IC4-PC1(ADC1)-Pad24)") (class "Default")
      (node (ref "IC4") (pin "24") (pinfunction "PC1(ADC1)_24") (pintype "bidirectional"))
    )
    (net (code "77") (name "unconnected-(IC4-PC2(ADC2)-Pad25)") (class "Default")
      (node (ref "IC4") (pin "25") (pinfunction "PC2(ADC2)_25") (pintype "bidirectional"))
    )
    (net (code "78") (name "unconnected-(IC4-PC5(ADC5{slash}SCL)-Pad28)") (class "Default")
      (node (ref "IC4") (pin "28") (pinfunction "PC5(ADC5/SCL)_28") (pintype "bidirectional"))
    )
    (net (code "79") (name "unconnected-(IC4-PD5(T1)-Pad9)") (class "Default")
      (node (ref "IC4") (pin "9") (pinfunction "PD5(T1)_9") (pintype "bidirectional"))
    )
    (net (code "80") (name "unconnected-(IC4-PD6(AIN0)-Pad10)") (class "Default")
      (node (ref "IC4") (pin "10") (pinfunction "PD6(AIN0)_10") (pintype "bidirectional"))
    )
    (net (code "81") (name "{slash}CS1") (class "Default")
      (node (ref "B1") (pin "/CS1") (pinfunction "/CS1_/CS1") (pintype "bidirectional"))
      (node (ref "IC1") (pin "6") (pinfunction "Y2_6") (pintype "output"))
    )
    (net (code "82") (name "{slash}CS2") (class "Default")
      (node (ref "B1") (pin "/CS2") (pinfunction "/CS2_/CS2") (pintype "bidirectional"))
      (node (ref "IC1") (pin "5") (pinfunction "Y1_5") (pintype "output"))
    )
    (net (code "83") (name "{slash}CS3") (class "Default")
      (node (ref "IC1") (pin "7") (pinfunction "Y3_7") (pintype "output"))
      (node (ref "IC4") (pin "14") (pinfunction "PB2(SS/OC1B)_14") (pintype "bidirectional"))
    )
  )
)
